# JSB_Schematic.net
KiCad netlist of a schematic drawn in Altium Designer
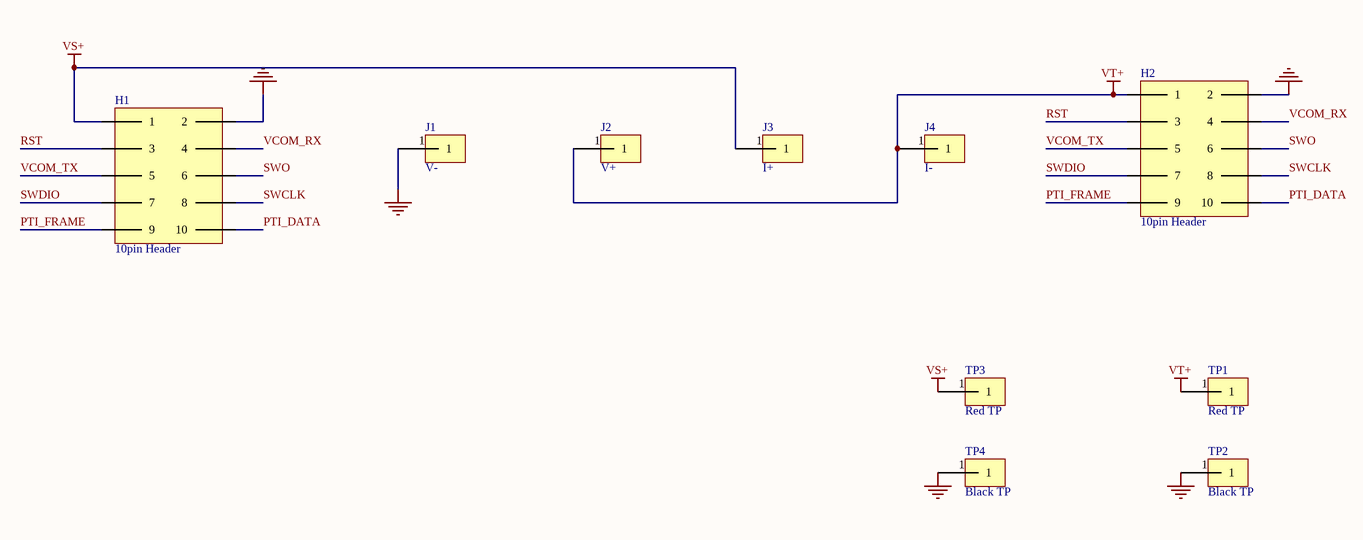
[diagram p0: JSB_Schematic.SchDoc]

(export (version "E")
  (design (tool "Eeschema 10.0.6"))
  (components
    (comp (ref "H1")
      (value "10pin Header")
      (footprint "20021121")
      (description "10 Pin Mini Header")
      (fields
        (field (name "MANUFACTURER") "Amphenol ICC / FCI")
        (field (name "MANUFACTURER PART NUMBER") "20021121-00010C4LF")
      )
      (libsource (lib "JSB_SchLib") (part "20021121-00010C4LF"))
    )
    (comp (ref "H2")
      (value "10pin Header")
      (footprint "20021121")
      (description "10 Pin Mini Header")
      (fields
        (field (name "MANUFACTURER") "Amphenol ICC / FCI")
        (field (name "MANUFACTURER PART NUMBER") "20021121-00010C4LF")
      )
      (libsource (lib "JSB_SchLib") (part "20021121-00010C4LF"))
    )
    (comp (ref "J1")
      (value "V-")
      (footprint "654")
      (description "CONN BANANA PLUG THRD")
      (fields
        (field (name "MANUFACTURER") "Keystone Electronics")
        (field (name "MANUFACTURER PART NUMBER") "654")
      )
      (libsource (lib "JSB_SchLib") (part "654"))
    )
    (comp (ref "J2")
      (value "V+")
      (footprint "654")
      (description "CONN BANANA PLUG THRD")
      (fields
        (field (name "MANUFACTURER") "Keystone Electronics")
        (field (name "MANUFACTURER PART NUMBER") "654")
      )
      (libsource (lib "JSB_SchLib") (part "654"))
    )
    (comp (ref "J3")
      (value "I+")
      (footprint "654")
      (description "CONN BANANA PLUG THRD")
      (fields
        (field (name "MANUFACTURER") "Keystone Electronics")
        (field (name "MANUFACTURER PART NUMBER") "654")
      )
      (libsource (lib "JSB_SchLib") (part "654"))
    )
    (comp (ref "J4")
      (value "I-")
      (footprint "654")
      (description "CONN BANANA PLUG THRD")
      (fields
        (field (name "MANUFACTURER") "Keystone Electronics")
        (field (name "MANUFACTURER PART NUMBER") "654")
      )
      (libsource (lib "JSB_SchLib") (part "654"))
    )
    (comp (ref "TP1")
      (value "Red TP")
      (footprint "5190TR")
      (description "RED SMD Test Point")
      (fields
        (field (name "MANUFACTURER") "Keystone Electronics")
        (field (name "MANUFACTURER PART NUMBER") "5190TR")
      )
      (libsource (lib "JSB_SchLib") (part "5190TR"))
    )
    (comp (ref "TP2")
      (value "Black TP")
      (footprint "5191TR")
      (description "BLACK SMD Test Point")
      (fields
        (field (name "MANUFACTURER") "Keystone Electronics")
        (field (name "MANUFACTURER PART NUMBER") "5191TR")
      )
      (libsource (lib "JSB_SchLib") (part "5191TR"))
    )
    (comp (ref "TP3")
      (value "Red TP")
      (footprint "5190TR")
      (description "RED SMD Test Point")
      (fields
        (field (name "MANUFACTURER") "Keystone Electronics")
        (field (name "MANUFACTURER PART NUMBER") "5190TR")
      )
      (libsource (lib "JSB_SchLib") (part "5190TR"))
    )
    (comp (ref "TP4")
      (value "Black TP")
      (footprint "5191TR")
      (description "BLACK SMD Test Point")
      (fields
        (field (name "MANUFACTURER") "Keystone Electronics")
        (field (name "MANUFACTURER PART NUMBER") "5191TR")
      )
      (libsource (lib "JSB_SchLib") (part "5191TR"))
    )
  )
  (nets
    (net (code "1") (name "/PTI_DATA") (class "Default")
      (node (ref "H1") (pin "10") (pinfunction "10_10") (pintype "passive"))
      (node (ref "H2") (pin "10") (pinfunction "10_10") (pintype "passive"))
    )
    (net (code "2") (name "/PTI_FRAME") (class "Default")
      (node (ref "H1") (pin "9") (pinfunction "9_9") (pintype "passive"))
      (node (ref "H2") (pin "9") (pinfunction "9_9") (pintype "passive"))
    )
    (net (code "3") (name "/RST") (class "Default")
      (node (ref "H1") (pin "3") (pinfunction "3_3") (pintype "passive"))
      (node (ref "H2") (pin "3") (pinfunction "3_3") (pintype "passive"))
    )
    (net (code "4") (name "/SWCLK") (class "Default")
      (node (ref "H1") (pin "8") (pinfunction "8_8") (pintype "passive"))
      (node (ref "H2") (pin "8") (pinfunction "8_8") (pintype "passive"))
    )
    (net (code "5") (name "/SWDIO") (class "Default")
      (node (ref "H1") (pin "7") (pinfunction "7_7") (pintype "passive"))
      (node (ref "H2") (pin "7") (pinfunction "7_7") (pintype "passive"))
    )
    (net (code "6") (name "/SWO") (class "Default")
      (node (ref "H1") (pin "6") (pinfunction "6_6") (pintype "passive"))
      (node (ref "H2") (pin "6") (pinfunction "6_6") (pintype "passive"))
    )
    (net (code "7") (name "/VCOM_RX") (class "Default")
      (node (ref "H1") (pin "4") (pinfunction "4_4") (pintype "passive"))
      (node (ref "H2") (pin "4") (pinfunction "4_4") (pintype "passive"))
    )
    (net (code "8") (name "/VCOM_TX") (class "Default")
      (node (ref "H1") (pin "5") (pinfunction "5_5") (pintype "passive"))
      (node (ref "H2") (pin "5") (pinfunction "5_5") (pintype "passive"))
    )
    (net (code "9") (name "GND") (class "Default")
      (node (ref "H1") (pin "2") (pinfunction "2_2") (pintype "passive"))
      (node (ref "H2") (pin "2") (pinfunction "2_2") (pintype "passive"))
      (node (ref "J1") (pin "1") (pinfunction "1_1") (pintype "passive"))
      (node (ref "TP2") (pin "1") (pinfunction "1_1") (pintype "passive"))
      (node (ref "TP4") (pin "1") (pinfunction "1_1") (pintype "passive"))
    )
    (net (code "10") (name "VS+") (class "Default")
      (node (ref "H1") (pin "1") (pinfunction "1_1") (pintype "passive"))
      (node (ref "J3") (pin "1") (pinfunction "1_1") (pintype "passive"))
      (node (ref "TP3") (pin "1") (pinfunction "1_1") (pintype "passive"))
    )
    (net (code "11") (name "VT+") (class "Default")
      (node (ref "H2") (pin "1") (pinfunction "1_1") (pintype "passive"))
      (node (ref "J2") (pin "1") (pinfunction "1_1") (pintype "passive"))
      (node (ref "J4") (pin "1") (pinfunction "1_1") (pintype "passive"))
      (node (ref "TP1") (pin "1") (pinfunction "1_1") (pintype "passive"))
    )
  )
)
